# ME433.net
KiCad netlist of a schematic drawn in EAGLE
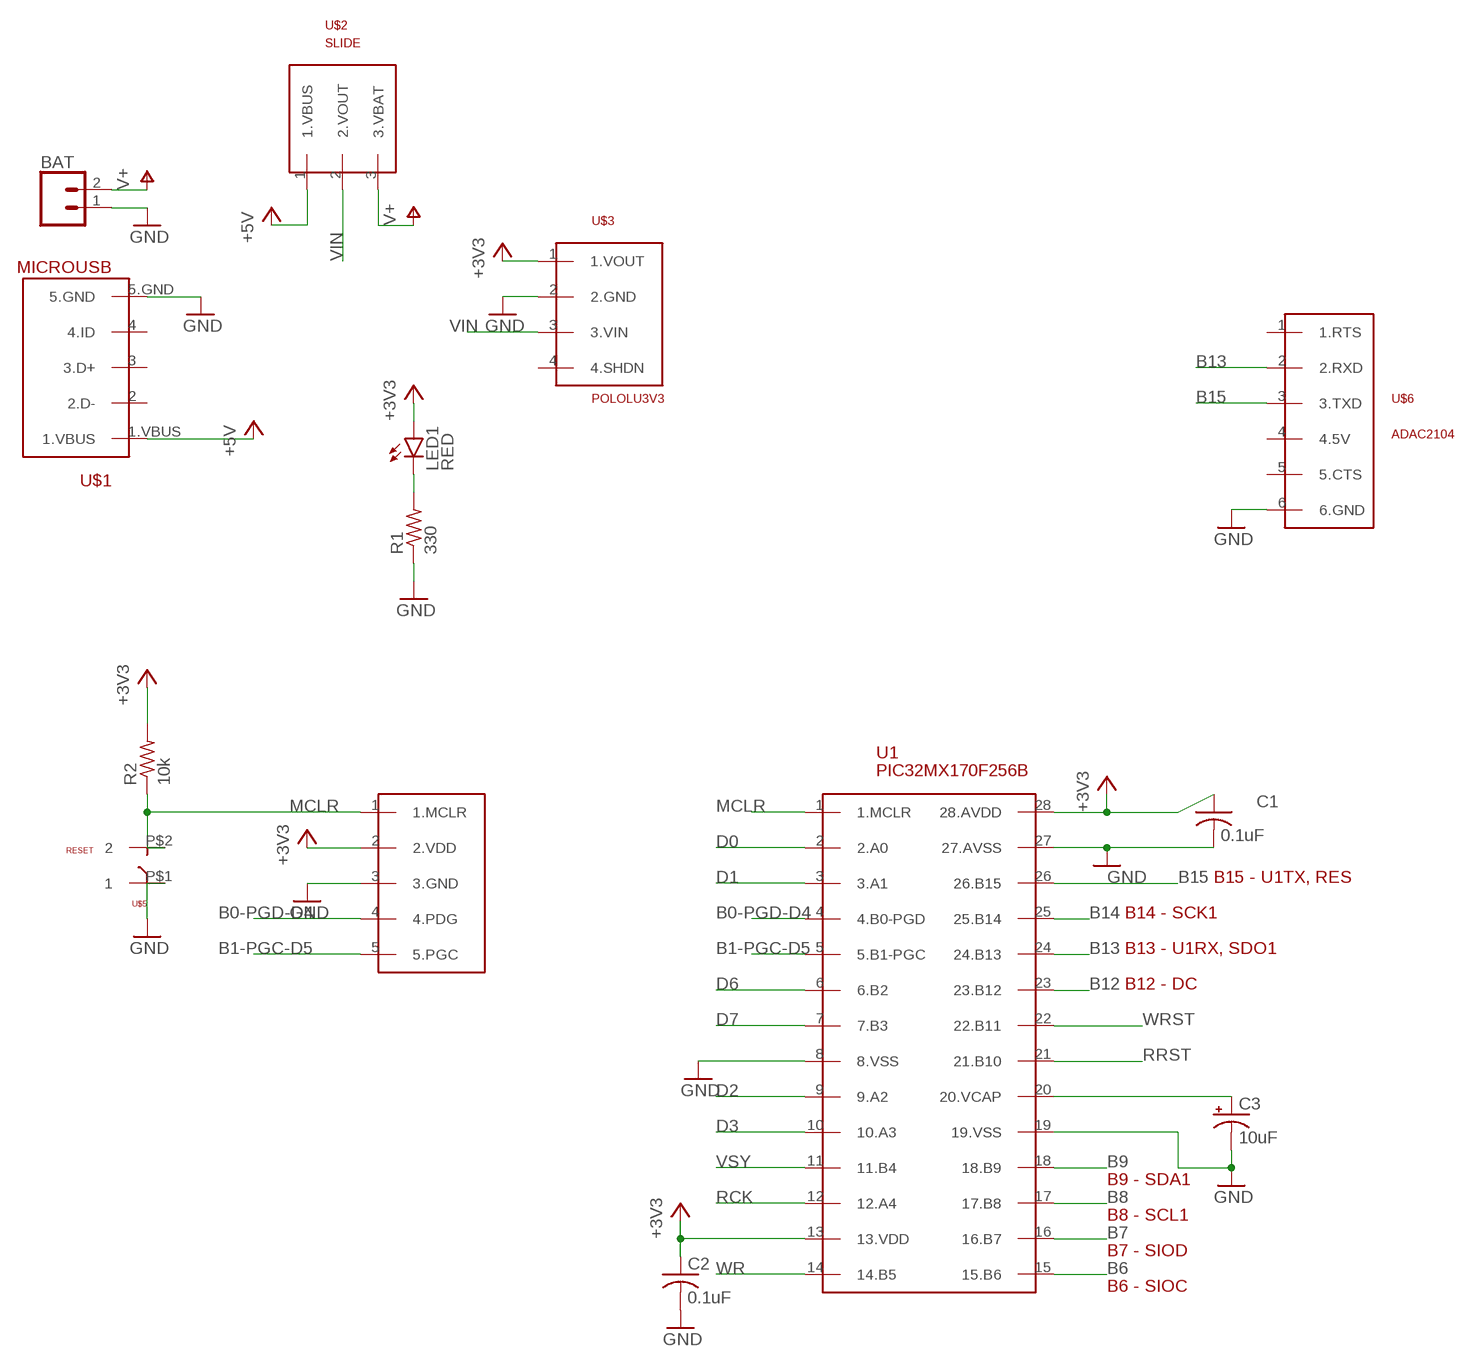
[diagram p0: schematic, sheet 1, part 1 of 2]
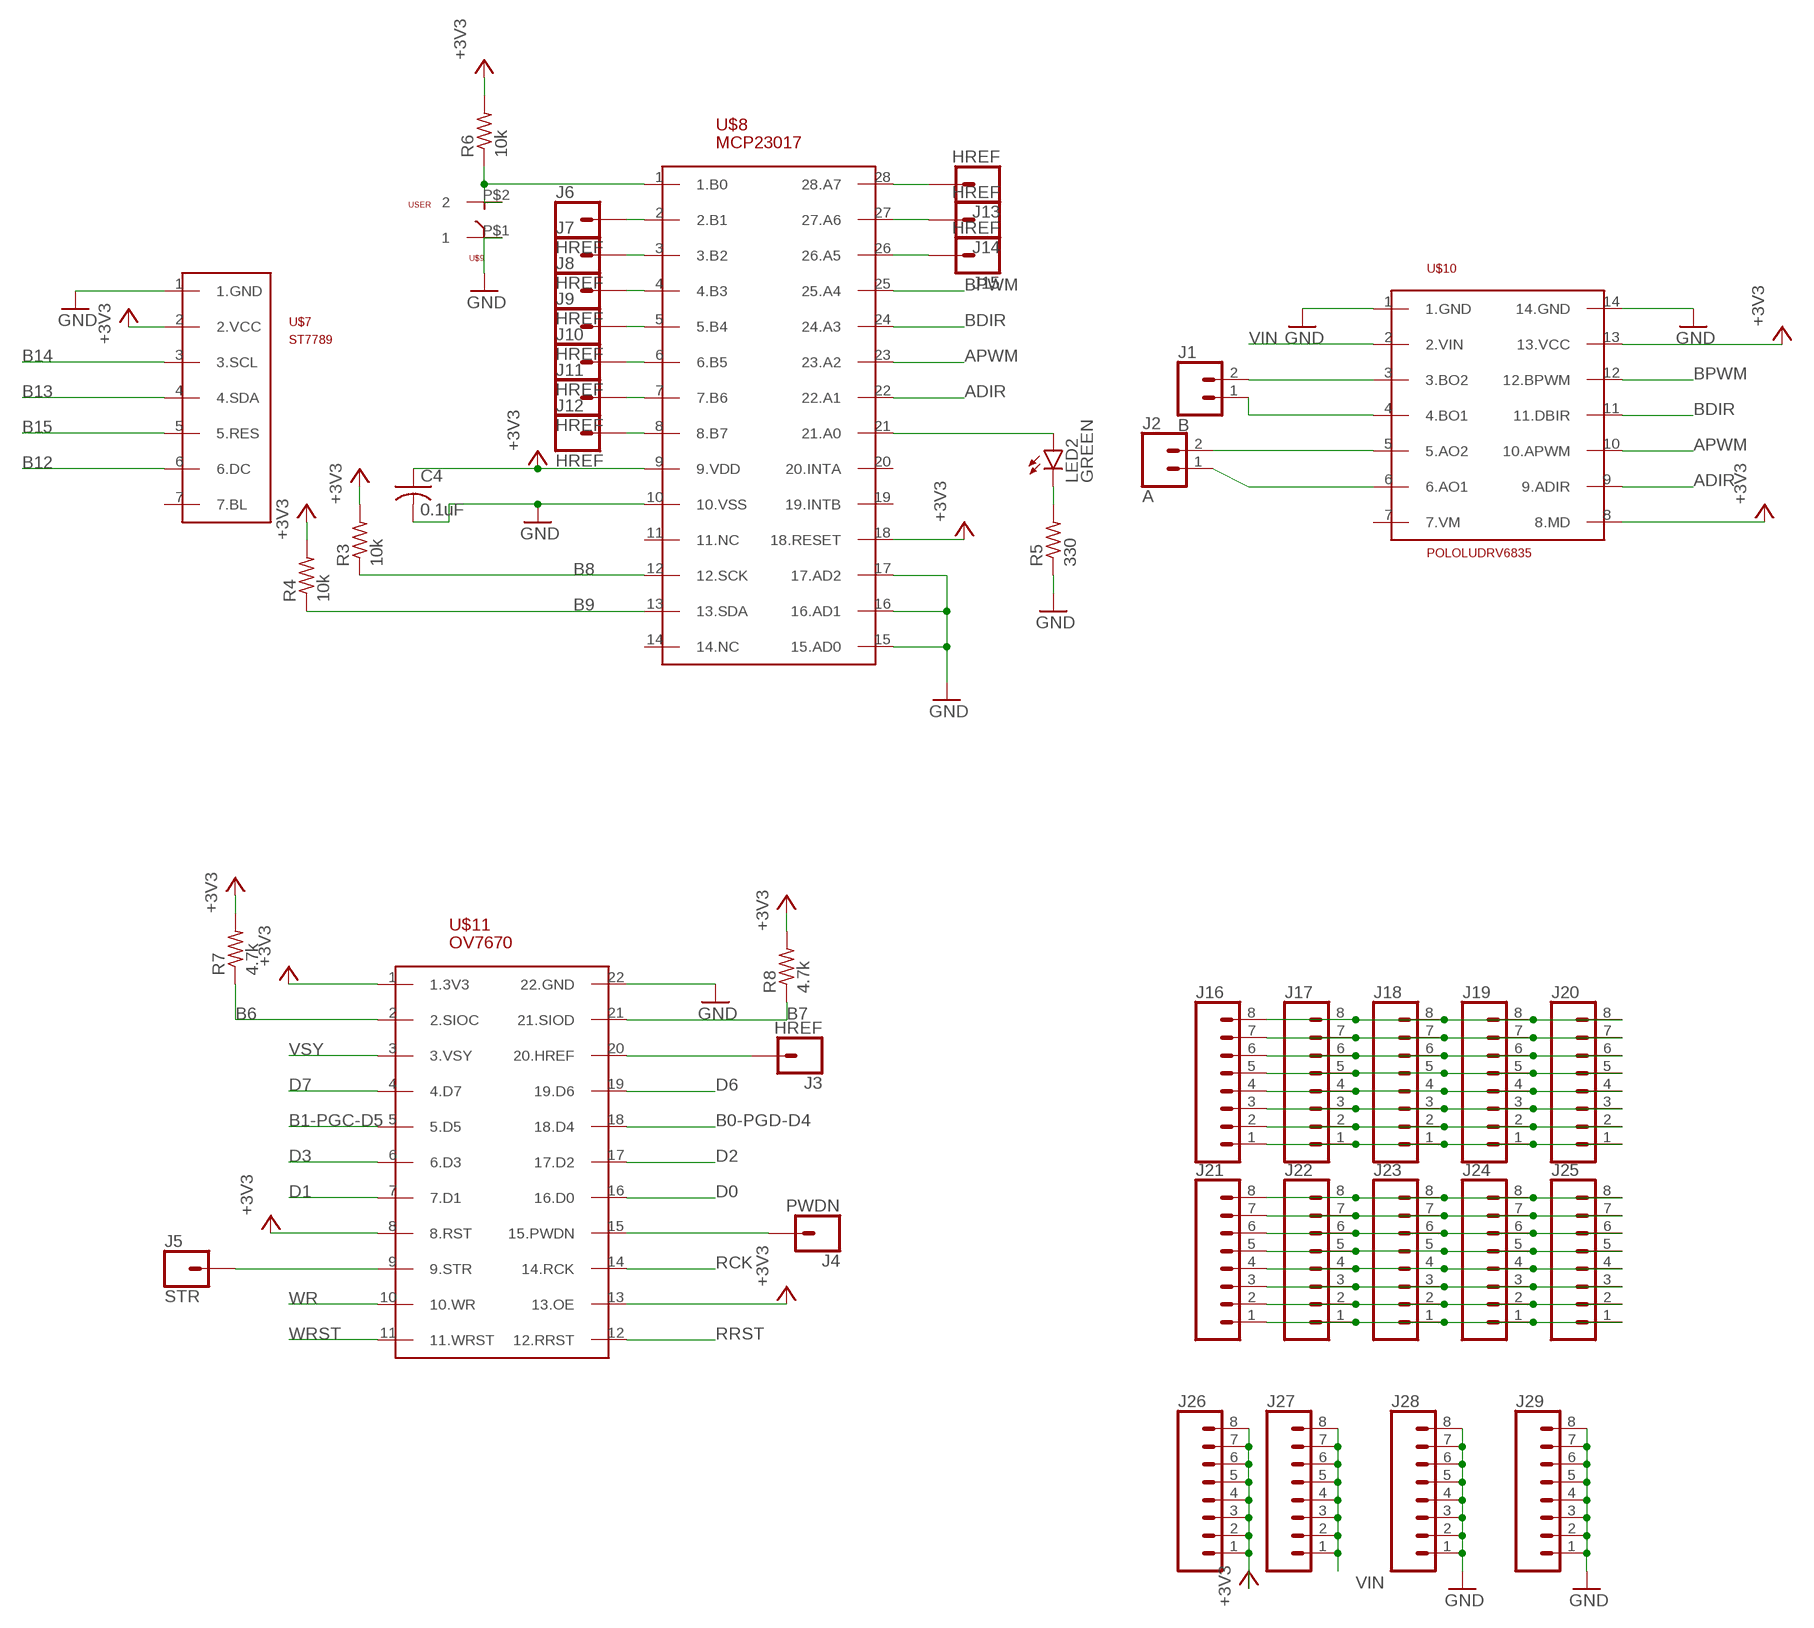
[diagram p1: schematic, sheet 1, part 2 of 2]

(export (version "E")
  (design (tool "Eeschema 10.0.6"))
  (components
    (comp (ref "BAT")
      (value "CONN_02")
      (footprint "eagle-import:1X02")
      (libsource (lib "eagle-import") (part "CONN_02"))
    )
    (comp (ref "C1")
      (value "0.1uF")
      (footprint "eagle-import:C025-030X050")
      (libsource (lib "eagle-import") (part "C-US025-030X050"))
    )
    (comp (ref "C2")
      (value "0.1uF")
      (footprint "eagle-import:C025-030X050")
      (libsource (lib "eagle-import") (part "C-US025-030X050"))
    )
    (comp (ref "C3")
      (value "10uF")
      (footprint "eagle-import:B45181B")
      (libsource (lib "eagle-import") (part "CPOL-USB45181B"))
    )
    (comp (ref "C4")
      (value "0.1uF")
      (footprint "eagle-import:C025-030X050")
      (libsource (lib "eagle-import") (part "C-US025-030X050"))
    )
    (comp (ref "J1")
      (value "B")
      (footprint "eagle-import:1X02")
      (libsource (lib "eagle-import") (part "CONN_02"))
    )
    (comp (ref "J2")
      (value "A")
      (footprint "eagle-import:1X02")
      (libsource (lib "eagle-import") (part "CONN_02"))
    )
    (comp (ref "J3")
      (value "HREF")
      (footprint "eagle-import:1X01")
      (libsource (lib "eagle-import") (part "CONN_01"))
    )
    (comp (ref "J4")
      (value "PWDN")
      (footprint "eagle-import:1X01")
      (libsource (lib "eagle-import") (part "CONN_01"))
    )
    (comp (ref "J5")
      (value "STR")
      (footprint "eagle-import:1X01")
      (libsource (lib "eagle-import") (part "CONN_01"))
    )
    (comp (ref "J6")
      (value "HREF")
      (footprint "eagle-import:1X01")
      (libsource (lib "eagle-import") (part "CONN_01"))
    )
    (comp (ref "J7")
      (value "HREF")
      (footprint "eagle-import:1X01")
      (libsource (lib "eagle-import") (part "CONN_01"))
    )
    (comp (ref "J8")
      (value "HREF")
      (footprint "eagle-import:1X01")
      (libsource (lib "eagle-import") (part "CONN_01"))
    )
    (comp (ref "J9")
      (value "HREF")
      (footprint "eagle-import:1X01")
      (libsource (lib "eagle-import") (part "CONN_01"))
    )
    (comp (ref "J10")
      (value "HREF")
      (footprint "eagle-import:1X01")
      (libsource (lib "eagle-import") (part "CONN_01"))
    )
    (comp (ref "J11")
      (value "HREF")
      (footprint "eagle-import:1X01")
      (libsource (lib "eagle-import") (part "CONN_01"))
    )
    (comp (ref "J12")
      (value "HREF")
      (footprint "eagle-import:1X01")
      (libsource (lib "eagle-import") (part "CONN_01"))
    )
    (comp (ref "J13")
      (value "HREF")
      (footprint "eagle-import:1X01")
      (libsource (lib "eagle-import") (part "CONN_01"))
    )
    (comp (ref "J14")
      (value "HREF")
      (footprint "eagle-import:1X01")
      (libsource (lib "eagle-import") (part "CONN_01"))
    )
    (comp (ref "J15")
      (value "HREF")
      (footprint "eagle-import:1X01")
      (libsource (lib "eagle-import") (part "CONN_01"))
    )
    (comp (ref "J16")
      (value "CONN_08\"")
      (footprint "eagle-import:1X08")
      (libsource (lib "eagle-import") (part "CONN_08{dblquote}"))
    )
    (comp (ref "J17")
      (value "CONN_08\"")
      (footprint "eagle-import:1X08")
      (libsource (lib "eagle-import") (part "CONN_08{dblquote}"))
    )
    (comp (ref "J18")
      (value "CONN_08\"")
      (footprint "eagle-import:1X08")
      (libsource (lib "eagle-import") (part "CONN_08{dblquote}"))
    )
    (comp (ref "J19")
      (value "CONN_08\"")
      (footprint "eagle-import:1X08")
      (libsource (lib "eagle-import") (part "CONN_08{dblquote}"))
    )
    (comp (ref "J20")
      (value "CONN_08\"")
      (footprint "eagle-import:1X08")
      (libsource (lib "eagle-import") (part "CONN_08{dblquote}"))
    )
    (comp (ref "J21")
      (value "CONN_08\"")
      (footprint "eagle-import:1X08")
      (libsource (lib "eagle-import") (part "CONN_08{dblquote}"))
    )
    (comp (ref "J22")
      (value "CONN_08\"")
      (footprint "eagle-import:1X08")
      (libsource (lib "eagle-import") (part "CONN_08{dblquote}"))
    )
    (comp (ref "J23")
      (value "CONN_08\"")
      (footprint "eagle-import:1X08")
      (libsource (lib "eagle-import") (part "CONN_08{dblquote}"))
    )
    (comp (ref "J24")
      (value "CONN_08\"")
      (footprint "eagle-import:1X08")
      (libsource (lib "eagle-import") (part "CONN_08{dblquote}"))
    )
    (comp (ref "J25")
      (value "CONN_08\"")
      (footprint "eagle-import:1X08")
      (libsource (lib "eagle-import") (part "CONN_08{dblquote}"))
    )
    (comp (ref "J26")
      (value "CONN_08\"")
      (footprint "eagle-import:1X08")
      (libsource (lib "eagle-import") (part "CONN_08{dblquote}"))
    )
    (comp (ref "J27")
      (value "CONN_08\"")
      (footprint "eagle-import:1X08")
      (libsource (lib "eagle-import") (part "CONN_08{dblquote}"))
    )
    (comp (ref "J28")
      (value "CONN_08\"")
      (footprint "eagle-import:1X08")
      (libsource (lib "eagle-import") (part "CONN_08{dblquote}"))
    )
    (comp (ref "J29")
      (value "CONN_08\"")
      (footprint "eagle-import:1X08")
      (libsource (lib "eagle-import") (part "CONN_08{dblquote}"))
    )
    (comp (ref "LED1")
      (value "RED")
      (footprint "eagle-import:LED3MM")
      (libsource (lib "eagle-import") (part "LED3MM"))
    )
    (comp (ref "LED2")
      (value "GREEN")
      (footprint "eagle-import:LED3MM")
      (libsource (lib "eagle-import") (part "LED3MM"))
    )
    (comp (ref "R1")
      (value "330")
      (footprint "eagle-import:0207_10")
      (libsource (lib "eagle-import") (part "R-US_0207/10"))
    )
    (comp (ref "R2")
      (value "10k")
      (footprint "eagle-import:0207_10")
      (libsource (lib "eagle-import") (part "R-US_0207/10"))
    )
    (comp (ref "R3")
      (value "10k")
      (footprint "eagle-import:0207_10")
      (libsource (lib "eagle-import") (part "R-US_0207/10"))
    )
    (comp (ref "R4")
      (value "10k")
      (footprint "eagle-import:0207_10")
      (libsource (lib "eagle-import") (part "R-US_0207/10"))
    )
    (comp (ref "R5")
      (value "330")
      (footprint "eagle-import:0207_10")
      (libsource (lib "eagle-import") (part "R-US_0207/10"))
    )
    (comp (ref "R6")
      (value "10k")
      (footprint "eagle-import:0207_10")
      (libsource (lib "eagle-import") (part "R-US_0207/10"))
    )
    (comp (ref "R7")
      (value "4.7k")
      (footprint "eagle-import:0207_10")
      (libsource (lib "eagle-import") (part "R-US_0207/10"))
    )
    (comp (ref "R8")
      (value "4.7k")
      (footprint "eagle-import:0207_10")
      (libsource (lib "eagle-import") (part "R-US_0207/10"))
    )
    (comp (ref "U$1")
      (value "MICROUSB")
      (footprint "eagle-import:MICROUSB")
      (libsource (lib "eagle-import") (part "MICROUSB"))
    )
    (comp (ref "U$2")
      (value "SLIDE")
      (footprint "eagle-import:SLIDE")
      (libsource (lib "eagle-import") (part "SLIDE"))
    )
    (comp (ref "U$3")
      (value "POLOLU3V3")
      (footprint "eagle-import:POLOLU3V3")
      (libsource (lib "eagle-import") (part "POLOLU3V3"))
    )
    (comp (ref "U$4")
      (value "SNAP")
      (footprint "eagle-import:SNAP")
      (libsource (lib "eagle-import") (part "SNAP"))
    )
    (comp (ref "U$5")
      (value "RESET")
      (footprint "eagle-import:PUSH")
      (libsource (lib "eagle-import") (part "PUSH"))
    )
    (comp (ref "U$6")
      (value "ADAC2104")
      (footprint "eagle-import:ADAC2104")
      (libsource (lib "eagle-import") (part "ADAC2104"))
    )
    (comp (ref "U$7")
      (value "ST7789")
      (footprint "eagle-import:ST7789")
      (libsource (lib "eagle-import") (part "ST7789"))
    )
    (comp (ref "U$8")
      (value "MCP23017")
      (footprint "eagle-import:DIL28-3")
      (libsource (lib "eagle-import") (part "MCP23017"))
    )
    (comp (ref "U$9")
      (value "USER")
      (footprint "eagle-import:PUSH")
      (libsource (lib "eagle-import") (part "PUSH"))
    )
    (comp (ref "U$10")
      (value "POLOLUDRV6835")
      (footprint "eagle-import:POLOLUDRV6835")
      (libsource (lib "eagle-import") (part "POLOLUDRV6835"))
    )
    (comp (ref "U$11")
      (value "OV7670")
      (footprint "eagle-import:OV7670")
      (libsource (lib "eagle-import") (part "OV7670"))
    )
    (comp (ref "U1")
      (value "PIC32MX170F256B")
      (footprint "eagle-import:DIL28-3")
      (libsource (lib "eagle-import") (part "PIC32MX170F256B"))
    )
  )
  (nets
    (net (code "1") (name "+3V3") (class "Default")
      (node (ref "C1") (pin "1") (pinfunction "1_1") (pintype "passive"))
      (node (ref "C2") (pin "1") (pinfunction "1_1") (pintype "passive"))
      (node (ref "C4") (pin "1") (pinfunction "1_1") (pintype "passive"))
      (node (ref "J26") (pin "1") (pinfunction "1_1") (pintype "passive"))
      (node (ref "J26") (pin "2") (pinfunction "2_2") (pintype "passive"))
      (node (ref "J26") (pin "3") (pinfunction "3_3") (pintype "passive"))
      (node (ref "J26") (pin "4") (pinfunction "4_4") (pintype "passive"))
      (node (ref "J26") (pin "5") (pinfunction "5_5") (pintype "passive"))
      (node (ref "J26") (pin "6") (pinfunction "6_6") (pintype "passive"))
      (node (ref "J26") (pin "7") (pinfunction "7_7") (pintype "passive"))
      (node (ref "J26") (pin "8") (pinfunction "8_8") (pintype "passive"))
      (node (ref "LED1") (pin "A") (pinfunction "A_A") (pintype "passive"))
      (node (ref "R2") (pin "2") (pinfunction "2_2") (pintype "passive"))
      (node (ref "R3") (pin "2") (pinfunction "2_2") (pintype "passive"))
      (node (ref "R4") (pin "2") (pinfunction "2_2") (pintype "passive"))
      (node (ref "R6") (pin "2") (pinfunction "2_2") (pintype "passive"))
      (node (ref "R7") (pin "2") (pinfunction "2_2") (pintype "passive"))
      (node (ref "R8") (pin "2") (pinfunction "2_2") (pintype "passive"))
      (node (ref "U$10") (pin "13") (pinfunction "13.VCC_13") (pintype "bidirectional"))
      (node (ref "U$10") (pin "8") (pinfunction "8.MD_8") (pintype "bidirectional"))
      (node (ref "U$11") (pin "1") (pinfunction "1.3V3_1") (pintype "bidirectional"))
      (node (ref "U$11") (pin "13") (pinfunction "13.OE_13") (pintype "bidirectional"))
      (node (ref "U$11") (pin "8") (pinfunction "8.RST_8") (pintype "bidirectional"))
      (node (ref "U$3") (pin "1") (pinfunction "1.VOUT_1") (pintype "bidirectional"))
      (node (ref "U$4") (pin "2") (pinfunction "2.VDD_2") (pintype "bidirectional"))
      (node (ref "U$7") (pin "2") (pinfunction "2.VCC_2") (pintype "bidirectional"))
      (node (ref "U$8") (pin "18") (pinfunction "18.RESET_18") (pintype "bidirectional"))
      (node (ref "U$8") (pin "9") (pinfunction "9.VDD_9") (pintype "bidirectional"))
      (node (ref "U1") (pin "13") (pinfunction "13.VDD_13") (pintype "bidirectional"))
      (node (ref "U1") (pin "28") (pinfunction "28.AVDD_28") (pintype "bidirectional"))
    )
    (net (code "2") (name "+5V") (class "Default")
      (node (ref "U$1") (pin "1.VBUS") (pinfunction "1.VBUS_1.VBUS") (pintype "bidirectional"))
      (node (ref "U$2") (pin "1") (pinfunction "1.VBUS_1") (pintype "bidirectional"))
    )
    (net (code "3") (name "/ADIR") (class "Default")
      (node (ref "U$10") (pin "9") (pinfunction "9.ADIR_9") (pintype "bidirectional"))
      (node (ref "U$8") (pin "22") (pinfunction "22.A1_22") (pintype "bidirectional"))
    )
    (net (code "4") (name "/APWM") (class "Default")
      (node (ref "U$10") (pin "10") (pinfunction "10.APWM_10") (pintype "bidirectional"))
      (node (ref "U$8") (pin "23") (pinfunction "23.A2_23") (pintype "bidirectional"))
    )
    (net (code "5") (name "/B0-PGD-D4") (class "Default")
      (node (ref "U$11") (pin "18") (pinfunction "18.D4_18") (pintype "bidirectional"))
      (node (ref "U$4") (pin "4") (pinfunction "4.PDG_4") (pintype "bidirectional"))
      (node (ref "U1") (pin "4") (pinfunction "4.B0-PGD_4") (pintype "bidirectional"))
    )
    (net (code "6") (name "/B1-PGC-D5") (class "Default")
      (node (ref "U$11") (pin "5") (pinfunction "5.D5_5") (pintype "bidirectional"))
      (node (ref "U$4") (pin "5") (pinfunction "5.PGC_5") (pintype "bidirectional"))
      (node (ref "U1") (pin "5") (pinfunction "5.B1-PGC_5") (pintype "bidirectional"))
    )
    (net (code "7") (name "/B6") (class "Default")
      (node (ref "R7") (pin "1") (pinfunction "1_1") (pintype "passive"))
      (node (ref "U$11") (pin "2") (pinfunction "2.SIOC_2") (pintype "bidirectional"))
      (node (ref "U1") (pin "15") (pinfunction "15.B6_15") (pintype "bidirectional"))
    )
    (net (code "8") (name "/B7") (class "Default")
      (node (ref "R8") (pin "1") (pinfunction "1_1") (pintype "passive"))
      (node (ref "U$11") (pin "21") (pinfunction "21.SIOD_21") (pintype "bidirectional"))
      (node (ref "U1") (pin "16") (pinfunction "16.B7_16") (pintype "bidirectional"))
    )
    (net (code "9") (name "/B8") (class "Default")
      (node (ref "R3") (pin "1") (pinfunction "1_1") (pintype "passive"))
      (node (ref "U$8") (pin "12") (pinfunction "12.SCK_12") (pintype "bidirectional"))
      (node (ref "U1") (pin "17") (pinfunction "17.B8_17") (pintype "bidirectional"))
    )
    (net (code "10") (name "/B9") (class "Default")
      (node (ref "R4") (pin "1") (pinfunction "1_1") (pintype "passive"))
      (node (ref "U$8") (pin "13") (pinfunction "13.SDA_13") (pintype "bidirectional"))
      (node (ref "U1") (pin "18") (pinfunction "18.B9_18") (pintype "bidirectional"))
    )
    (net (code "11") (name "/B12") (class "Default")
      (node (ref "U$7") (pin "6") (pinfunction "6.DC_6") (pintype "bidirectional"))
      (node (ref "U1") (pin "23") (pinfunction "23.B12_23") (pintype "bidirectional"))
    )
    (net (code "12") (name "/B13") (class "Default")
      (node (ref "U$6") (pin "2") (pinfunction "2.RXD_2") (pintype "bidirectional"))
      (node (ref "U$7") (pin "4") (pinfunction "4.SDA_4") (pintype "bidirectional"))
      (node (ref "U1") (pin "24") (pinfunction "24.B13_24") (pintype "bidirectional"))
    )
    (net (code "13") (name "/B14") (class "Default")
      (node (ref "U$7") (pin "3") (pinfunction "3.SCL_3") (pintype "bidirectional"))
      (node (ref "U1") (pin "25") (pinfunction "25.B14_25") (pintype "bidirectional"))
    )
    (net (code "14") (name "/B15") (class "Default")
      (node (ref "U$6") (pin "3") (pinfunction "3.TXD_3") (pintype "bidirectional"))
      (node (ref "U$7") (pin "5") (pinfunction "5.RES_5") (pintype "bidirectional"))
      (node (ref "U1") (pin "26") (pinfunction "26.B15_26") (pintype "bidirectional"))
    )
    (net (code "15") (name "/BDIR") (class "Default")
      (node (ref "U$10") (pin "11") (pinfunction "11.DBIR_11") (pintype "bidirectional"))
      (node (ref "U$8") (pin "24") (pinfunction "24.A3_24") (pintype "bidirectional"))
    )
    (net (code "16") (name "/BPWM") (class "Default")
      (node (ref "U$10") (pin "12") (pinfunction "12.BPWM_12") (pintype "bidirectional"))
      (node (ref "U$8") (pin "25") (pinfunction "25.A4_25") (pintype "bidirectional"))
    )
    (net (code "17") (name "/D0") (class "Default")
      (node (ref "U$11") (pin "16") (pinfunction "16.D0_16") (pintype "bidirectional"))
      (node (ref "U1") (pin "2") (pinfunction "2.A0_2") (pintype "bidirectional"))
    )
    (net (code "18") (name "/D1") (class "Default")
      (node (ref "U$11") (pin "7") (pinfunction "7.D1_7") (pintype "bidirectional"))
      (node (ref "U1") (pin "3") (pinfunction "3.A1_3") (pintype "bidirectional"))
    )
    (net (code "19") (name "/D2") (class "Default")
      (node (ref "U$11") (pin "17") (pinfunction "17.D2_17") (pintype "bidirectional"))
      (node (ref "U1") (pin "9") (pinfunction "9.A2_9") (pintype "bidirectional"))
    )
    (net (code "20") (name "/D3") (class "Default")
      (node (ref "U$11") (pin "6") (pinfunction "6.D3_6") (pintype "bidirectional"))
      (node (ref "U1") (pin "10") (pinfunction "10.A3_10") (pintype "bidirectional"))
    )
    (net (code "21") (name "/D6") (class "Default")
      (node (ref "U$11") (pin "19") (pinfunction "19.D6_19") (pintype "bidirectional"))
      (node (ref "U1") (pin "6") (pinfunction "6.B2_6") (pintype "bidirectional"))
    )
    (net (code "22") (name "/D7") (class "Default")
      (node (ref "U$11") (pin "4") (pinfunction "4.D7_4") (pintype "bidirectional"))
      (node (ref "U1") (pin "7") (pinfunction "7.B3_7") (pintype "bidirectional"))
    )
    (net (code "23") (name "/MCLR") (class "Default")
      (node (ref "R2") (pin "1") (pinfunction "1_1") (pintype "passive"))
      (node (ref "U$4") (pin "1") (pinfunction "1.MCLR_1") (pintype "bidirectional"))
      (node (ref "U$5") (pin "P$2") (pinfunction "2_P$2") (pintype "bidirectional"))
      (node (ref "U1") (pin "1") (pinfunction "1.MCLR_1") (pintype "bidirectional"))
    )
    (net (code "24") (name "/RCK") (class "Default")
      (node (ref "U$11") (pin "14") (pinfunction "14.RCK_14") (pintype "bidirectional"))
      (node (ref "U1") (pin "12") (pinfunction "12.A4_12") (pintype "bidirectional"))
    )
    (net (code "25") (name "/RRST") (class "Default")
      (node (ref "U$11") (pin "12") (pinfunction "12.RRST_12") (pintype "bidirectional"))
      (node (ref "U1") (pin "21") (pinfunction "21.B10_21") (pintype "bidirectional"))
    )
    (net (code "26") (name "/VIN") (class "Default")
      (node (ref "J27") (pin "1") (pinfunction "1_1") (pintype "passive"))
      (node (ref "J27") (pin "2") (pinfunction "2_2") (pintype "passive"))
      (node (ref "J27") (pin "3") (pinfunction "3_3") (pintype "passive"))
      (node (ref "J27") (pin "4") (pinfunction "4_4") (pintype "passive"))
      (node (ref "J27") (pin "5") (pinfunction "5_5") (pintype "passive"))
      (node (ref "J27") (pin "6") (pinfunction "6_6") (pintype "passive"))
      (node (ref "J27") (pin "7") (pinfunction "7_7") (pintype "passive"))
      (node (ref "J27") (pin "8") (pinfunction "8_8") (pintype "passive"))
      (node (ref "U$10") (pin "2") (pinfunction "2.VIN_2") (pintype "bidirectional"))
      (node (ref "U$2") (pin "2") (pinfunction "2.VOUT_2") (pintype "bidirectional"))
      (node (ref "U$3") (pin "3") (pinfunction "3.VIN_3") (pintype "bidirectional"))
    )
    (net (code "27") (name "/VSY") (class "Default")
      (node (ref "U$11") (pin "3") (pinfunction "3.VSY_3") (pintype "bidirectional"))
      (node (ref "U1") (pin "11") (pinfunction "11.B4_11") (pintype "bidirectional"))
    )
    (net (code "28") (name "/WR") (class "Default")
      (node (ref "U$11") (pin "10") (pinfunction "10.WR_10") (pintype "bidirectional"))
      (node (ref "U1") (pin "14") (pinfunction "14.B5_14") (pintype "bidirectional"))
    )
    (net (code "29") (name "/WRST") (class "Default")
      (node (ref "U$11") (pin "11") (pinfunction "11.WRST_11") (pintype "bidirectional"))
      (node (ref "U1") (pin "22") (pinfunction "22.B11_22") (pintype "bidirectional"))
    )
    (net (code "30") (name "GND") (class "Default")
      (node (ref "BAT") (pin "1") (pinfunction "1_1") (pintype "passive"))
      (node (ref "C1") (pin "2") (pinfunction "2_2") (pintype "passive"))
      (node (ref "C2") (pin "2") (pinfunction "2_2") (pintype "passive"))
      (node (ref "C3") (pin "-") (pinfunction "-_-") (pintype "passive"))
      (node (ref "C4") (pin "2") (pinfunction "2_2") (pintype "passive"))
      (node (ref "J28") (pin "1") (pinfunction "1_1") (pintype "passive"))
      (node (ref "J28") (pin "2") (pinfunction "2_2") (pintype "passive"))
      (node (ref "J28") (pin "3") (pinfunction "3_3") (pintype "passive"))
      (node (ref "J28") (pin "4") (pinfunction "4_4") (pintype "passive"))
      (node (ref "J28") (pin "5") (pinfunction "5_5") (pintype "passive"))
      (node (ref "J28") (pin "6") (pinfunction "6_6") (pintype "passive"))
      (node (ref "J28") (pin "7") (pinfunction "7_7") (pintype "passive"))
      (node (ref "J28") (pin "8") (pinfunction "8_8") (pintype "passive"))
      (node (ref "J29") (pin "1") (pinfunction "1_1") (pintype "passive"))
      (node (ref "J29") (pin "2") (pinfunction "2_2") (pintype "passive"))
      (node (ref "J29") (pin "3") (pinfunction "3_3") (pintype "passive"))
      (node (ref "J29") (pin "4") (pinfunction "4_4") (pintype "passive"))
      (node (ref "J29") (pin "5") (pinfunction "5_5") (pintype "passive"))
      (node (ref "J29") (pin "6") (pinfunction "6_6") (pintype "passive"))
      (node (ref "J29") (pin "7") (pinfunction "7_7") (pintype "passive"))
      (node (ref "J29") (pin "8") (pinfunction "8_8") (pintype "passive"))
      (node (ref "R1") (pin "1") (pinfunction "1_1") (pintype "passive"))
      (node (ref "R5") (pin "1") (pinfunction "1_1") (pintype "passive"))
      (node (ref "U$1") (pin "5.GND") (pinfunction "5.GND_5.GND") (pintype "bidirectional"))
      (node (ref "U$10") (pin "1") (pinfunction "1.GND_1") (pintype "bidirectional"))
      (node (ref "U$10") (pin "14") (pinfunction "14.GND_14") (pintype "bidirectional"))
      (node (ref "U$11") (pin "22") (pinfunction "22.GND_22") (pintype "bidirectional"))
      (node (ref "U$3") (pin "2") (pinfunction "2.GND_2") (pintype "bidirectional"))
      (node (ref "U$4") (pin "3") (pinfunction "3.GND_3") (pintype "bidirectional"))
      (node (ref "U$5") (pin "P$1") (pinfunction "1_P$1") (pintype "bidirectional"))
      (node (ref "U$6") (pin "6") (pinfunction "6.GND_6") (pintype "bidirectional"))
      (node (ref "U$7") (pin "1") (pinfunction "1.GND_1") (pintype "bidirectional"))
      (node (ref "U$8") (pin "10") (pinfunction "10.VSS_10") (pintype "bidirectional"))
      (node (ref "U$8") (pin "15") (pinfunction "15.AD0_15") (pintype "bidirectional"))
      (node (ref "U$8") (pin "16") (pinfunction "16.AD1_16") (pintype "bidirectional"))
      (node (ref "U$8") (pin "17") (pinfunction "17.AD2_17") (pintype "bidirectional"))
      (node (ref "U$9") (pin "P$1") (pinfunction "1_P$1") (pintype "bidirectional"))
      (node (ref "U1") (pin "19") (pinfunction "19.VSS_19") (pintype "bidirectional"))
      (node (ref "U1") (pin "27") (pinfunction "27.AVSS_27") (pintype "bidirectional"))
      (node (ref "U1") (pin "8") (pinfunction "8.VSS_8") (pintype "bidirectional"))
    )
    (net (code "31") (name "Net-(J16-Pad1)") (class "Default")
      (node (ref "J16") (pin "1") (pinfunction "1_1") (pintype "passive"))
      (node (ref "J17") (pin "1") (pinfunction "1_1") (pintype "passive"))
      (node (ref "J18") (pin "1") (pinfunction "1_1") (pintype "passive"))
      (node (ref "J19") (pin "1") (pinfunction "1_1") (pintype "passive"))
      (node (ref "J20") (pin "1") (pinfunction "1_1") (pintype "passive"))
    )
    (net (code "32") (name "Net-(J16-Pad2)") (class "Default")
      (node (ref "J16") (pin "2") (pinfunction "2_2") (pintype "passive"))
      (node (ref "J17") (pin "2") (pinfunction "2_2") (pintype "passive"))
      (node (ref "J18") (pin "2") (pinfunction "2_2") (pintype "passive"))
      (node (ref "J19") (pin "2") (pinfunction "2_2") (pintype "passive"))
      (node (ref "J20") (pin "2") (pinfunction "2_2") (pintype "passive"))
    )
    (net (code "33") (name "Net-(J16-Pad3)") (class "Default")
      (node (ref "J16") (pin "3") (pinfunction "3_3") (pintype "passive"))
      (node (ref "J17") (pin "3") (pinfunction "3_3") (pintype "passive"))
      (node (ref "J18") (pin "3") (pinfunction "3_3") (pintype "passive"))
      (node (ref "J19") (pin "3") (pinfunction "3_3") (pintype "passive"))
      (node (ref "J20") (pin "3") (pinfunction "3_3") (pintype "passive"))
    )
    (net (code "34") (name "Net-(J16-Pad4)") (class "Default")
      (node (ref "J16") (pin "4") (pinfunction "4_4") (pintype "passive"))
      (node (ref "J17") (pin "4") (pinfunction "4_4") (pintype "passive"))
      (node (ref "J18") (pin "4") (pinfunction "4_4") (pintype "passive"))
      (node (ref "J19") (pin "4") (pinfunction "4_4") (pintype "passive"))
      (node (ref "J20") (pin "4") (pinfunction "4_4") (pintype "passive"))
    )
    (net (code "35") (name "Net-(J16-Pad5)") (class "Default")
      (node (ref "J16") (pin "5") (pinfunction "5_5") (pintype "passive"))
      (node (ref "J17") (pin "5") (pinfunction "5_5") (pintype "passive"))
      (node (ref "J18") (pin "5") (pinfunction "5_5") (pintype "passive"))
      (node (ref "J19") (pin "5") (pinfunction "5_5") (pintype "passive"))
      (node (ref "J20") (pin "5") (pinfunction "5_5") (pintype "passive"))
    )
    (net (code "36") (name "Net-(J16-Pad6)") (class "Default")
      (node (ref "J16") (pin "6") (pinfunction "6_6") (pintype "passive"))
      (node (ref "J17") (pin "6") (pinfunction "6_6") (pintype "passive"))
      (node (ref "J18") (pin "6") (pinfunction "6_6") (pintype "passive"))
      (node (ref "J19") (pin "6") (pinfunction "6_6") (pintype "passive"))
      (node (ref "J20") (pin "6") (pinfunction "6_6") (pintype "passive"))
    )
    (net (code "37") (name "Net-(J16-Pad7)") (class "Default")
      (node (ref "J16") (pin "7") (pinfunction "7_7") (pintype "passive"))
      (node (ref "J17") (pin "7") (pinfunction "7_7") (pintype "passive"))
      (node (ref "J18") (pin "7") (pinfunction "7_7") (pintype "passive"))
      (node (ref "J19") (pin "7") (pinfunction "7_7") (pintype "passive"))
      (node (ref "J20") (pin "7") (pinfunction "7_7") (pintype "passive"))
    )
    (net (code "38") (name "Net-(J16-Pad8)") (class "Default")
      (node (ref "J16") (pin "8") (pinfunction "8_8") (pintype "passive"))
      (node (ref "J17") (pin "8") (pinfunction "8_8") (pintype "passive"))
      (node (ref "J18") (pin "8") (pinfunction "8_8") (pintype "passive"))
      (node (ref "J19") (pin "8") (pinfunction "8_8") (pintype "passive"))
      (node (ref "J20") (pin "8") (pinfunction "8_8") (pintype "passive"))
    )
    (net (code "39") (name "Net-(J21-Pad1)") (class "Default")
      (node (ref "J21") (pin "1") (pinfunction "1_1") (pintype "passive"))
      (node (ref "J22") (pin "1") (pinfunction "1_1") (pintype "passive"))
      (node (ref "J23") (pin "1") (pinfunction "1_1") (pintype "passive"))
      (node (ref "J24") (pin "1") (pinfunction "1_1") (pintype "passive"))
      (node (ref "J25") (pin "1") (pinfunction "1_1") (pintype "passive"))
    )
    (net (code "40") (name "Net-(J21-Pad2)") (class "Default")
      (node (ref "J21") (pin "2") (pinfunction "2_2") (pintype "passive"))
      (node (ref "J22") (pin "2") (pinfunction "2_2") (pintype "passive"))
      (node (ref "J23") (pin "2") (pinfunction "2_2") (pintype "passive"))
      (node (ref "J24") (pin "2") (pinfunction "2_2") (pintype "passive"))
      (node (ref "J25") (pin "2") (pinfunction "2_2") (pintype "passive"))
    )
    (net (code "41") (name "Net-(J21-Pad3)") (class "Default")
      (node (ref "J21") (pin "3") (pinfunction "3_3") (pintype "passive"))
      (node (ref "J22") (pin "3") (pinfunction "3_3") (pintype "passive"))
      (node (ref "J23") (pin "3") (pinfunction "3_3") (pintype "passive"))
      (node (ref "J24") (pin "3") (pinfunction "3_3") (pintype "passive"))
      (node (ref "J25") (pin "3") (pinfunction "3_3") (pintype "passive"))
    )
    (net (code "42") (name "Net-(J21-Pad4)") (class "Default")
      (node (ref "J21") (pin "4") (pinfunction "4_4") (pintype "passive"))
      (node (ref "J22") (pin "4") (pinfunction "4_4") (pintype "passive"))
      (node (ref "J23") (pin "4") (pinfunction "4_4") (pintype "passive"))
      (node (ref "J24") (pin "4") (pinfunction "4_4") (pintype "passive"))
      (node (ref "J25") (pin "4") (pinfunction "4_4") (pintype "passive"))
    )
    (net (code "43") (name "Net-(J21-Pad5)") (class "Default")
      (node (ref "J21") (pin "5") (pinfunction "5_5") (pintype "passive"))
      (node (ref "J22") (pin "5") (pinfunction "5_5") (pintype "passive"))
      (node (ref "J23") (pin "5") (pinfunction "5_5") (pintype "passive"))
      (node (ref "J24") (pin "5") (pinfunction "5_5") (pintype "passive"))
      (node (ref "J25") (pin "5") (pinfunction "5_5") (pintype "passive"))
    )
    (net (code "44") (name "Net-(J21-Pad6)") (class "Default")
      (node (ref "J21") (pin "6") (pinfunction "6_6") (pintype "passive"))
      (node (ref "J22") (pin "6") (pinfunction "6_6") (pintype "passive"))
      (node (ref "J23") (pin "6") (pinfunction "6_6") (pintype "passive"))
      (node (ref "J24") (pin "6") (pinfunction "6_6") (pintype "passive"))
      (node (ref "J25") (pin "6") (pinfunction "6_6") (pintype "passive"))
    )
    (net (code "45") (name "Net-(J21-Pad7)") (class "Default")
      (node (ref "J21") (pin "7") (pinfunction "7_7") (pintype "passive"))
      (node (ref "J22") (pin "7") (pinfunction "7_7") (pintype "passive"))
      (node (ref "J23") (pin "7") (pinfunction "7_7") (pintype "passive"))
      (node (ref "J24") (pin "7") (pinfunction "7_7") (pintype "passive"))
      (node (ref "J25") (pin "7") (pinfunction "7_7") (pintype "passive"))
    )
    (net (code "46") (name "Net-(J21-Pad8)") (class "Default")
      (node (ref "J21") (pin "8") (pinfunction "8_8") (pintype "passive"))
      (node (ref "J22") (pin "8") (pinfunction "8_8") (pintype "passive"))
      (node (ref "J23") (pin "8") (pinfunction "8_8") (pintype "passive"))
      (node (ref "J24") (pin "8") (pinfunction "8_8") (pintype "passive"))
      (node (ref "J25") (pin "8") (pinfunction "8_8") (pintype "passive"))
    )
    (net (code "47") (name "Net-(LED1-C)") (class "Default")
      (node (ref "LED1") (pin "K") (pinfunction "C_K") (pintype "passive"))
      (node (ref "R1") (pin "2") (pinfunction "2_2") (pintype "passive"))
    )
    (net (code "48") (name "Net-(LED2-C)") (class "Default")
      (node (ref "LED2") (pin "K") (pinfunction "C_K") (pintype "passive"))
      (node (ref "R5") (pin "2") (pinfunction "2_2") (pintype "passive"))
    )
    (net (code "49") (name "Net-(U$8-1.B0)") (class "Default")
      (node (ref "R6") (pin "1") (pinfunction "1_1") (pintype "passive"))
      (node (ref "U$8") (pin "1") (pinfunction "1.B0_1") (pintype "bidirectional"))
      (node (ref "U$9") (pin "P$2") (pinfunction "2_P$2") (pintype "bidirectional"))
    )
    (net (code "50") (name "Net-(U$8-2.B1)") (class "Default")
      (node (ref "J6") (pin "1") (pinfunction "1_1") (pintype "passive"))
      (node (ref "U$8") (pin "2") (pinfunction "2.B1_2") (pintype "bidirectional"))
    )
    (net (code "51") (name "Net-(U$8-3.B2)") (class "Default")
      (node (ref "J7") (pin "1") (pinfunction "1_1") (pintype "passive"))
      (node (ref "U$8") (pin "3") (pinfunction "3.B2_3") (pintype "bidirectional"))
    )
    (net (code "52") (name "Net-(U$8-4.B3)") (class "Default")
      (node (ref "J8") (pin "1") (pinfunction "1_1") (pintype "passive"))
      (node (ref "U$8") (pin "4") (pinfunction "4.B3_4") (pintype "bidirectional"))
    )
    (net (code "53") (name "Net-(U$8-5.B4)") (class "Default")
      (node (ref "J9") (pin "1") (pinfunction "1_1") (pintype "passive"))
      (node (ref "U$8") (pin "5") (pinfunction "5.B4_5") (pintype "bidirectional"))
    )
    (net (code "54") (name "Net-(U$8-6.B5)") (class "Default")
      (node (ref "J10") (pin "1") (pinfunction "1_1") (pintype "passive"))
      (node (ref "U$8") (pin "6") (pinfunction "6.B5_6") (pintype "bidirectional"))
    )
    (net (code "55") (name "Net-(U$8-7.B6)") (class "Default")
      (node (ref "J11") (pin "1") (pinfunction "1_1") (pintype "passive"))
      (node (ref "U$8") (pin "7") (pinfunction "7.B6_7") (pintype "bidirectional"))
    )
    (net (code "56") (name "Net-(U$8-8.B7)") (class "Default")
      (node (ref "J12") (pin "1") (pinfunction "1_1") (pintype "passive"))
      (node (ref "U$8") (pin "8") (pinfunction "8.B7_8") (pintype "bidirectional"))
    )
    (net (code "57") (name "Net-(U$8-21.A0)") (class "Default")
      (node (ref "LED2") (pin "A") (pinfunction "A_A") (pintype "passive"))
      (node (ref "U$8") (pin "21") (pinfunction "21.A0_21") (pintype "bidirectional"))
    )
    (net (code "58") (name "Net-(U$8-26.A5)") (class "Default")
      (node (ref "J15") (pin "1") (pinfunction "1_1") (pintype "passive"))
      (node (ref "U$8") (pin "26") (pinfunction "26.A5_26") (pintype "bidirectional"))
    )
    (net (code "59") (name "Net-(U$8-27.A6)") (class "Default")
      (node (ref "J14") (pin "1") (pinfunction "1_1") (pintype "passive"))
      (node (ref "U$8") (pin "27") (pinfunction "27.A6_27") (pintype "bidirectional"))
    )
    (net (code "60") (name "Net-(U$8-28.A7)") (class "Default")
      (node (ref "J13") (pin "1") (pinfunction "1_1") (pintype "passive"))
      (node (ref "U$8") (pin "28") (pinfunction "28.A7_28") (pintype "bidirectional"))
    )
    (net (code "61") (name "Net-(U$10-3.BO2)") (class "Default")
      (node (ref "J1") (pin "2") (pinfunction "2_2") (pintype "passive"))
      (node (ref "U$10") (pin "3") (pinfunction "3.BO2_3") (pintype "bidirectional"))
    )
    (net (code "62") (name "Net-(U$10-4.BO1)") (class "Default")
      (node (ref "J1") (pin "1") (pinfunction "1_1") (pintype "passive"))
      (node (ref "U$10") (pin "4") (pinfunction "4.BO1_4") (pintype "bidirectional"))
    )
    (net (code "63") (name "Net-(U$10-5.AO2)") (class "Default")
      (node (ref "J2") (pin "2") (pinfunction "2_2") (pintype "passive"))
      (node (ref "U$10") (pin "5") (pinfunction "5.AO2_5") (pintype "bidirectional"))
    )
    (net (code "64") (name "Net-(U$10-6.AO1)") (class "Default")
      (node (ref "J2") (pin "1") (pinfunction "1_1") (pintype "passive"))
      (node (ref "U$10") (pin "6") (pinfunction "6.AO1_6") (pintype "bidirectional"))
    )
    (net (code "65") (name "Net-(U$11-9.STR)") (class "Default")
      (node (ref "J5") (pin "1") (pinfunction "1_1") (pintype "passive"))
      (node (ref "U$11") (pin "9") (pinfunction "9.STR_9") (pintype "bidirectional"))
    )
    (net (code "66") (name "Net-(U$11-15.PWDN)") (class "Default")
      (node (ref "J4") (pin "1") (pinfunction "1_1") (pintype "passive"))
      (node (ref "U$11") (pin "15") (pinfunction "15.PWDN_15") (pintype "bidirectional"))
    )
    (net (code "67") (name "Net-(U$11-20.HREF)") (class "Default")
      (node (ref "J3") (pin "1") (pinfunction "1_1") (pintype "passive"))
      (node (ref "U$11") (pin "20") (pinfunction "20.HREF_20") (pintype "bidirectional"))
    )
    (net (code "68") (name "Net-(U1-20.VCAP)") (class "Default")
      (node (ref "C3") (pin "+") (pinfunction "+_+") (pintype "passive"))
      (node (ref "U1") (pin "20") (pinfunction "20.VCAP_20") (pintype "bidirectional"))
    )
    (net (code "69") (name "V+") (class "Default")
      (node (ref "BAT") (pin "2") (pinfunction "2_2") (pintype "passive"))
      (node (ref "U$2") (pin "3") (pinfunction "3.VBAT_3") (pintype "bidirectional"))
    )
    (net (code "70") (name "unconnected-(U$1-2.D--Pad2)") (class "Default")
      (node (ref "U$1") (pin "2") (pinfunction "2.D-_2") (pintype "bidirectional"))
    )
    (net (code "71") (name "unconnected-(U$1-3.D+-Pad3)") (class "Default")
      (node (ref "U$1") (pin "3") (pinfunction "3.D+_3") (pintype "bidirectional"))
    )
    (net (code "72") (name "unconnected-(U$1-4.ID-Pad4)") (class "Default")
      (node (ref "U$1") (pin "4") (pinfunction "4.ID_4") (pintype "bidirectional"))
    )
    (net (code "73") (name "unconnected-(U$3-4.SHDN-Pad4)") (class "Default")
      (node (ref "U$3") (pin "4") (pinfunction "4.SHDN_4") (pintype "bidirectional"))
    )
    (net (code "74") (name "unconnected-(U$6-1.RTS-Pad1)") (class "Default")
      (node (ref "U$6") (pin "1") (pinfunction "1.RTS_1") (pintype "bidirectional"))
    )
    (net (code "75") (name "unconnected-(U$6-4.5V-Pad4)") (class "Default")
      (node (ref "U$6") (pin "4") (pinfunction "4.5V_4") (pintype "bidirectional"))
    )
    (net (code "76") (name "unconnected-(U$6-5.CTS-Pad5)") (class "Default")
      (node (ref "U$6") (pin "5") (pinfunction "5.CTS_5") (pintype "bidirectional"))
    )
    (net (code "77") (name "unconnected-(U$7-7.BL-Pad7)") (class "Default")
      (node (ref "U$7") (pin "7") (pinfunction "7.BL_7") (pintype "bidirectional"))
    )
    (net (code "78") (name "unconnected-(U$8-11.NC-Pad11)") (class "Default")
      (node (ref "U$8") (pin "11") (pinfunction "11.NC_11") (pintype "bidirectional"))
    )
    (net (code "79") (name "unconnected-(U$8-14.NC-Pad14)") (class "Default")
      (node (ref "U$8") (pin "14") (pinfunction "14.NC_14") (pintype "bidirectional"))
    )
    (net (code "80") (name "unconnected-(U$8-19.INTB-Pad19)") (class "Default")
      (node (ref "U$8") (pin "19") (pinfunction "19.INTB_19") (pintype "bidirectional"))
    )
    (net (code "81") (name "unconnected-(U$8-20.INTA-Pad20)") (class "Default")
      (node (ref "U$8") (pin "20") (pinfunction "20.INTA_20") (pintype "bidirectional"))
    )
    (net (code "82") (name "unconnected-(U$10-7.VM-Pad7)") (class "Default")
      (node (ref "U$10") (pin "7") (pinfunction "7.VM_7") (pintype "bidirectional"))
    )
  )
)
